# switch.net
KiCad netlist of a schematic drawn in EAGLE
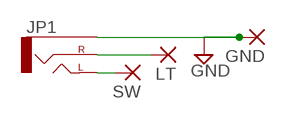
[diagram p0: schematic, sheet 1]

(export (version "E")
  (design (tool "Eeschema 10.0.6"))
  (components
    (comp (ref "GND")
      (value "2,15/1,0")
      (footprint "eagle-import:2,15_1,0")
      (libsource (lib "eagle-import") (part "2,15/1,0"))
    )
    (comp (ref "JP1")
      (value "AUDIO-JACKPTH")
      (footprint "eagle-import:AUDIO-JACK")
      (libsource (lib "eagle-import") (part "AUDIO-JACKPTH"))
    )
    (comp (ref "LT")
      (value "2,15/1,0")
      (footprint "eagle-import:2,15_1,0")
      (libsource (lib "eagle-import") (part "2,15/1,0"))
    )
    (comp (ref "SW")
      (value "2,15/1,0")
      (footprint "eagle-import:2,15_1,0")
      (libsource (lib "eagle-import") (part "2,15/1,0"))
    )
  )
  (nets
    (net (code "1") (name "GND") (class "Default")
      (node (ref "GND") (pin "1") (pinfunction "P_1") (pintype "passive"))
      (node (ref "JP1") (pin "SLEEVE") (pinfunction "SLEEVE_SLEEVE") (pintype "bidirectional"))
    )
    (net (code "2") (name "Net-(JP1-LEFT)") (class "Default")
      (node (ref "JP1") (pin "TIP") (pinfunction "LEFT_TIP") (pintype "bidirectional"))
      (node (ref "SW") (pin "1") (pinfunction "P_1") (pintype "passive"))
    )
    (net (code "3") (name "Net-(JP1-RIGHT)") (class "Default")
      (node (ref "JP1") (pin "RING") (pinfunction "RIGHT_RING") (pintype "bidirectional"))
      (node (ref "LT") (pin "1") (pinfunction "P_1") (pintype "passive"))
    )
  )
)
